# 130809_AriloTX_0_2.net
KiCad netlist of a schematic drawn in EAGLE
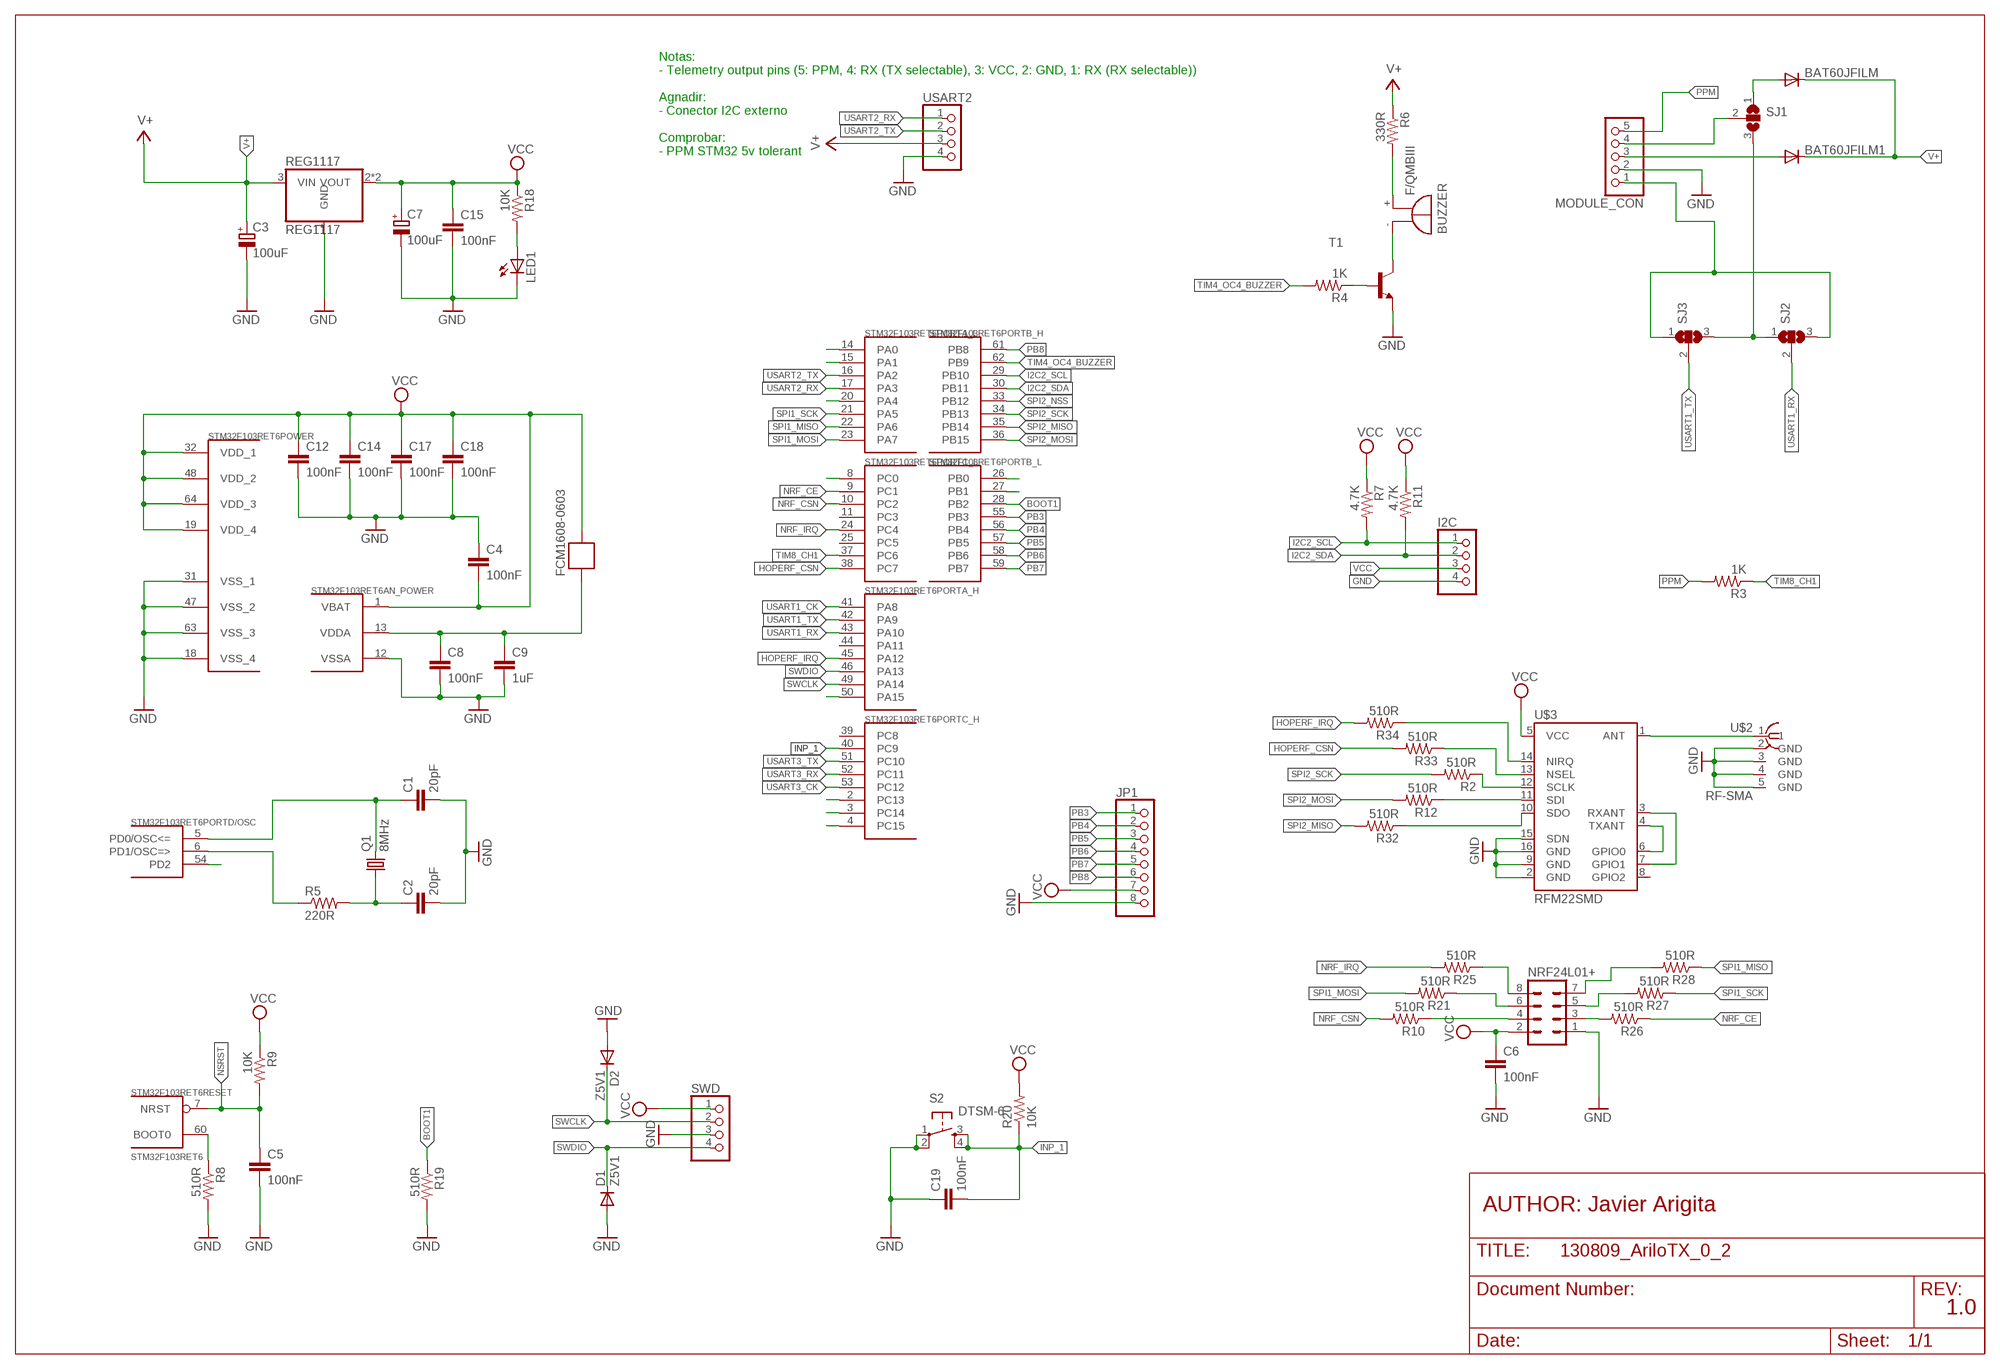
[diagram p0: schematic, sheet 1]

(export (version "E")
  (design (tool "Eeschema 10.0.6"))
  (components
    (comp (ref "BAT60JFILM")
      (value "DIODE-SOD323-R")
      (footprint "eagle-import:SOD323-R")
      (libsource (lib "eagle-import") (part "DIODE-SOD323-R"))
    )
    (comp (ref "BAT60JFILM1")
      (value "DIODE-SOD323-R")
      (footprint "eagle-import:SOD323-R")
      (libsource (lib "eagle-import") (part "DIODE-SOD323-R"))
    )
    (comp (ref "BUZZER")
      (value "F/QMBIII")
      (footprint "eagle-import:F_QMBIII")
      (libsource (lib "eagle-import") (part "F/QMBIII"))
    )
    (comp (ref "C1")
      (value "20pF")
      (footprint "eagle-import:C0805")
      (libsource (lib "eagle-import") (part "C-EUC0805"))
    )
    (comp (ref "C2")
      (value "20pF")
      (footprint "eagle-import:C0805")
      (libsource (lib "eagle-import") (part "C-EUC0805"))
    )
    (comp (ref "C3")
      (value "100uF")
      (footprint "eagle-import:SMC_B")
      (libsource (lib "eagle-import") (part "CPOL-EUSMCB"))
    )
    (comp (ref "C4")
      (value "100nF")
      (footprint "eagle-import:C0805")
      (libsource (lib "eagle-import") (part "C-EUC0805"))
    )
    (comp (ref "C5")
      (value "100nF")
      (footprint "eagle-import:C0805")
      (libsource (lib "eagle-import") (part "C-EUC0805"))
    )
    (comp (ref "C6")
      (value "100nF")
      (footprint "eagle-import:C0805")
      (libsource (lib "eagle-import") (part "C-EUC0805"))
    )
    (comp (ref "C7")
      (value "100uF")
      (footprint "eagle-import:SMC_B")
      (libsource (lib "eagle-import") (part "CPOL-EUSMCB"))
    )
    (comp (ref "C8")
      (value "100nF")
      (footprint "eagle-import:C0805")
      (libsource (lib "eagle-import") (part "C-EUC0805"))
    )
    (comp (ref "C9")
      (value "1uF")
      (footprint "eagle-import:C3216")
      (libsource (lib "eagle-import") (part "resistor_C-EUC3216"))
    )
    (comp (ref "C12")
      (value "100nF")
      (footprint "eagle-import:C0805")
      (libsource (lib "eagle-import") (part "C-EUC0805"))
    )
    (comp (ref "C14")
      (value "100nF")
      (footprint "eagle-import:C0805")
      (libsource (lib "eagle-import") (part "C-EUC0805"))
    )
    (comp (ref "C15")
      (value "100nF")
      (footprint "eagle-import:C0805")
      (libsource (lib "eagle-import") (part "C-EUC0805"))
    )
    (comp (ref "C17")
      (value "100nF")
      (footprint "eagle-import:C0805")
      (libsource (lib "eagle-import") (part "C-EUC0805"))
    )
    (comp (ref "C18")
      (value "100nF")
      (footprint "eagle-import:C0805")
      (libsource (lib "eagle-import") (part "C-EUC0805"))
    )
    (comp (ref "C19")
      (value "100nF")
      (footprint "eagle-import:C0805")
      (libsource (lib "eagle-import") (part "C-EUC0805"))
    )
    (comp (ref "D1")
      (value "Z5V1")
      (footprint "eagle-import:SOD323-R")
      (libsource (lib "eagle-import") (part "DIODE-SOD323-R"))
    )
    (comp (ref "D2")
      (value "Z5V1")
      (footprint "eagle-import:SOD323-R")
      (libsource (lib "eagle-import") (part "DIODE-SOD323-R"))
    )
    (comp (ref "FCM1608-0603")
      (value "FERRITE-BEAD")
      (footprint "eagle-import:R0603")
      (libsource (lib "eagle-import") (part "FERRITE-BEAD"))
    )
    (comp (ref "I2C")
      (value "PINHD-1X4")
      (footprint "eagle-import:1X04")
      (libsource (lib "eagle-import") (part "PINHD-1X4"))
    )
    (comp (ref "JP1")
      (value "PINHD-1X8")
      (footprint "eagle-import:1X08")
      (libsource (lib "eagle-import") (part "PINHD-1X8"))
    )
    (comp (ref "LED1")
      (value "LED0805")
      (footprint "eagle-import:CHIPLED_0805")
      (libsource (lib "eagle-import") (part "LED0805"))
    )
    (comp (ref "MODULE_CON")
      (value "PINHD-1X5")
      (footprint "eagle-import:1X05")
      (libsource (lib "eagle-import") (part "PINHD-1X5"))
    )
    (comp (ref "NRF24L01+")
      (value "MA04-2")
      (footprint "eagle-import:MA04-2")
      (libsource (lib "eagle-import") (part "MA04-2"))
    )
    (comp (ref "Q1")
      (value "8MHz")
      (footprint "eagle-import:SM49")
      (libsource (lib "eagle-import") (part "CRYSTALSM49"))
    )
    (comp (ref "R2")
      (value "510R")
      (footprint "eagle-import:R0805")
      (libsource (lib "eagle-import") (part "RESISTOR0805"))
    )
    (comp (ref "R3")
      (value "1K")
      (footprint "eagle-import:R0805")
      (libsource (lib "eagle-import") (part "RESISTOR0805"))
    )
    (comp (ref "R4")
      (value "1K")
      (footprint "eagle-import:R0805")
      (libsource (lib "eagle-import") (part "RESISTOR0805"))
    )
    (comp (ref "R5")
      (value "220R")
      (footprint "eagle-import:R0805")
      (libsource (lib "eagle-import") (part "RESISTOR0805"))
    )
    (comp (ref "R6")
      (value "330R")
      (footprint "eagle-import:R0805")
      (libsource (lib "eagle-import") (part "RESISTOR0805"))
    )
    (comp (ref "R7")
      (value "4.7K")
      (footprint "eagle-import:R0805")
      (libsource (lib "eagle-import") (part "RESISTOR0805"))
    )
    (comp (ref "R8")
      (value "510R")
      (footprint "eagle-import:R0805")
      (libsource (lib "eagle-import") (part "RESISTOR0805"))
    )
    (comp (ref "R9")
      (value "10K")
      (footprint "eagle-import:R0805")
      (libsource (lib "eagle-import") (part "RESISTOR0805"))
    )
    (comp (ref "R10")
      (value "510R")
      (footprint "eagle-import:R0805")
      (libsource (lib "eagle-import") (part "RESISTOR0805"))
    )
    (comp (ref "R11")
      (value "4.7K")
      (footprint "eagle-import:R0805")
      (libsource (lib "eagle-import") (part "RESISTOR0805"))
    )
    (comp (ref "R12")
      (value "510R")
      (footprint "eagle-import:R0805")
      (libsource (lib "eagle-import") (part "RESISTOR0805"))
    )
    (comp (ref "R18")
      (value "10K")
      (footprint "eagle-import:R0805")
      (libsource (lib "eagle-import") (part "RESISTOR0805"))
    )
    (comp (ref "R19")
      (value "510R")
      (footprint "eagle-import:R0805")
      (libsource (lib "eagle-import") (part "RESISTOR0805"))
    )
    (comp (ref "R20")
      (value "10K")
      (footprint "eagle-import:R0805")
      (libsource (lib "eagle-import") (part "RESISTOR0805"))
    )
    (comp (ref "R21")
      (value "510R")
      (footprint "eagle-import:R0805")
      (libsource (lib "eagle-import") (part "RESISTOR0805"))
    )
    (comp (ref "R25")
      (value "510R")
      (footprint "eagle-import:R0805")
      (libsource (lib "eagle-import") (part "RESISTOR0805"))
    )
    (comp (ref "R26")
      (value "510R")
      (footprint "eagle-import:R0805")
      (libsource (lib "eagle-import") (part "RESISTOR0805"))
    )
    (comp (ref "R27")
      (value "510R")
      (footprint "eagle-import:R0805")
      (libsource (lib "eagle-import") (part "RESISTOR0805"))
    )
    (comp (ref "R28")
      (value "510R")
      (footprint "eagle-import:R0805")
      (libsource (lib "eagle-import") (part "RESISTOR0805"))
    )
    (comp (ref "R32")
      (value "510R")
      (footprint "eagle-import:R0805")
      (libsource (lib "eagle-import") (part "RESISTOR0805"))
    )
    (comp (ref "R33")
      (value "510R")
      (footprint "eagle-import:R0805")
      (libsource (lib "eagle-import") (part "RESISTOR0805"))
    )
    (comp (ref "R34")
      (value "510R")
      (footprint "eagle-import:R0805")
      (libsource (lib "eagle-import") (part "RESISTOR0805"))
    )
    (comp (ref "REG1117")
      (value "REG1117")
      (footprint "eagle-import:SOT223")
      (libsource (lib "eagle-import") (part "REG1117"))
    )
    (comp (ref "S2")
      (value "DTSM-6")
      (footprint "eagle-import:DTSM-6")
      (libsource (lib "eagle-import") (part "DTSM-6"))
    )
    (comp (ref "SJ1")
      (value "SJ2W")
      (footprint "eagle-import:SJ_2")
      (libsource (lib "eagle-import") (part "SJ2W"))
    )
    (comp (ref "SJ2")
      (value "SJ2W")
      (footprint "eagle-import:SJ_2")
      (libsource (lib "eagle-import") (part "SJ2W"))
    )
    (comp (ref "SJ3")
      (value "SJ2W")
      (footprint "eagle-import:SJ_2")
      (libsource (lib "eagle-import") (part "SJ2W"))
    )
    (comp (ref "STM32F103RET6")
      (value "STM32F103RET6")
      (footprint "eagle-import:TQFP64")
      (libsource (lib "eagle-import") (part "STM32F10XRXT6"))
    )
    (comp (ref "SWD")
      (value "PINHD-1X4")
      (footprint "eagle-import:1X04")
      (libsource (lib "eagle-import") (part "PINHD-1X4"))
    )
    (comp (ref "T1")
      (value "BC848-NPN-SOT23-BEC")
      (footprint "eagle-import:SOT23-BEC")
      (libsource (lib "eagle-import") (part "-NPN-SOT23-BECBC848"))
    )
    (comp (ref "U$2")
      (value "RF-SMA")
      (footprint "eagle-import:BU-SMA-H")
      (libsource (lib "eagle-import") (part "RF-SMA"))
    )
    (comp (ref "U$3")
      (value "RFM22SMD")
      (footprint "eagle-import:RFM22-XXX-S2")
      (libsource (lib "eagle-import") (part "RFM22SMD"))
    )
    (comp (ref "USART2")
      (value "PINHD-1X4")
      (footprint "eagle-import:1X04")
      (libsource (lib "eagle-import") (part "PINHD-1X4"))
    )
  )
  (nets
    (net (code "1") (name "BOOT1") (class "Default")
      (node (ref "R19") (pin "1") (pinfunction "1_1") (pintype "passive"))
      (node (ref "STM32F103RET6") (pin "28") (pinfunction "PB2_28") (pintype "bidirectional"))
    )
    (net (code "2") (name "GND") (class "Default")
      (node (ref "C1") (pin "2") (pinfunction "2_2") (pintype "passive"))
      (node (ref "C12") (pin "2") (pinfunction "2_2") (pintype "passive"))
      (node (ref "C14") (pin "2") (pinfunction "2_2") (pintype "passive"))
      (node (ref "C15") (pin "2") (pinfunction "2_2") (pintype "passive"))
      (node (ref "C17") (pin "2") (pinfunction "2_2") (pintype "passive"))
      (node (ref "C18") (pin "2") (pinfunction "2_2") (pintype "passive"))
      (node (ref "C19") (pin "1") (pinfunction "1_1") (pintype "passive"))
      (node (ref "C2") (pin "2") (pinfunction "2_2") (pintype "passive"))
      (node (ref "C3") (pin "-") (pinfunction "-_-") (pintype "passive"))
      (node (ref "C4") (pin "1") (pinfunction "1_1") (pintype "passive"))
      (node (ref "C5") (pin "2") (pinfunction "2_2") (pintype "passive"))
      (node (ref "C6") (pin "2") (pinfunction "2_2") (pintype "passive"))
      (node (ref "C7") (pin "-") (pinfunction "-_-") (pintype "passive"))
      (node (ref "C8") (pin "2") (pinfunction "2_2") (pintype "passive"))
      (node (ref "C9") (pin "2") (pinfunction "2_2") (pintype "passive"))
      (node (ref "D1") (pin "A") (pinfunction "A_A") (pintype "passive"))
      (node (ref "D2") (pin "A") (pinfunction "A_A") (pintype "passive"))
      (node (ref "I2C") (pin "4") (pinfunction "4_4") (pintype "passive"))
      (node (ref "JP1") (pin "8") (pinfunction "8_8") (pintype "passive"))
      (node (ref "LED1") (pin "C") (pinfunction "C_C") (pintype "passive"))
      (node (ref "MODULE_CON") (pin "2") (pinfunction "2_2") (pintype "passive"))
      (node (ref "NRF24L01+") (pin "1") (pinfunction "1_1") (pintype "passive"))
      (node (ref "R19") (pin "2") (pinfunction "2_2") (pintype "passive"))
      (node (ref "R8") (pin "2") (pinfunction "2_2") (pintype "passive"))
      (node (ref "REG1117") (pin "1") (pinfunction "GND_1") (pintype "power_in"))
      (node (ref "S2") (pin "1") (pinfunction "1_1") (pintype "passive"))
      (node (ref "S2") (pin "2") (pinfunction "2_2") (pintype "passive"))
      (node (ref "STM32F103RET6") (pin "12") (pinfunction "VSSA_12") (pintype "power_in"))
      (node (ref "STM32F103RET6") (pin "18") (pinfunction "VSS_4_18") (pintype "power_in"))
      (node (ref "STM32F103RET6") (pin "31") (pinfunction "VSS_1_31") (pintype "power_in"))
      (node (ref "STM32F103RET6") (pin "47") (pinfunction "VSS_2_47") (pintype "power_in"))
      (node (ref "STM32F103RET6") (pin "63") (pinfunction "VSS_3_63") (pintype "power_in"))
      (node (ref "SWD") (pin "3") (pinfunction "3_3") (pintype "passive"))
      (node (ref "T1") (pin "E") (pinfunction "E_E") (pintype "passive"))
      (node (ref "U$2") (pin "2") (pinfunction "GND_2") (pintype "power_in"))
      (node (ref "U$2") (pin "3") (pinfunction "GND_3") (pintype "bidirectional"))
      (node (ref "U$2") (pin "4") (pinfunction "GND_4") (pintype "bidirectional"))
      (node (ref "U$2") (pin "5") (pinfunction "GND_5") (pintype "bidirectional"))
      (node (ref "U$3") (pin "15") (pinfunction "SDN_15") (pintype "input"))
      (node (ref "U$3") (pin "16") (pinfunction "GND_16") (pintype "power_in"))
      (node (ref "U$3") (pin "2") (pinfunction "GND_2") (pintype "power_in"))
      (node (ref "U$3") (pin "9") (pinfunction "GND_9") (pintype "power_in"))
      (node (ref "USART2") (pin "4") (pinfunction "4_4") (pintype "passive"))
    )
    (net (code "3") (name "HOPERF_CSN") (class "Default")
      (node (ref "R33") (pin "2") (pinfunction "2_2") (pintype "passive"))
      (node (ref "STM32F103RET6") (pin "38") (pinfunction "PC7_38") (pintype "bidirectional"))
    )
    (net (code "4") (name "HOPERF_IRQ") (class "Default")
      (node (ref "R34") (pin "2") (pinfunction "2_2") (pintype "passive"))
      (node (ref "STM32F103RET6") (pin "45") (pinfunction "PA12_45") (pintype "bidirectional"))
    )
    (net (code "5") (name "I2C2_SCL") (class "Default")
      (node (ref "I2C") (pin "1") (pinfunction "1_1") (pintype "passive"))
      (node (ref "R7") (pin "2") (pinfunction "2_2") (pintype "passive"))
      (node (ref "STM32F103RET6") (pin "29") (pinfunction "PB10_29") (pintype "bidirectional"))
    )
    (net (code "6") (name "I2C2_SDA") (class "Default")
      (node (ref "I2C") (pin "2") (pinfunction "2_2") (pintype "passive"))
      (node (ref "R11") (pin "2") (pinfunction "2_2") (pintype "passive"))
      (node (ref "STM32F103RET6") (pin "30") (pinfunction "PB11_30") (pintype "bidirectional"))
    )
    (net (code "7") (name "INP_1") (class "Default")
      (node (ref "C19") (pin "2") (pinfunction "2_2") (pintype "passive"))
      (node (ref "R20") (pin "1") (pinfunction "1_1") (pintype "passive"))
      (node (ref "S2") (pin "3") (pinfunction "3_3") (pintype "passive"))
      (node (ref "S2") (pin "4") (pinfunction "4_4") (pintype "passive"))
      (node (ref "STM32F103RET6") (pin "40") (pinfunction "PC9_40") (pintype "bidirectional"))
    )
    (net (code "8") (name "NRF_CE") (class "Default")
      (node (ref "R26") (pin "1") (pinfunction "1_1") (pintype "passive"))
      (node (ref "STM32F103RET6") (pin "9") (pinfunction "PC1_9") (pintype "bidirectional"))
    )
    (net (code "9") (name "NRF_CSN") (class "Default")
      (node (ref "R10") (pin "2") (pinfunction "2_2") (pintype "passive"))
      (node (ref "STM32F103RET6") (pin "10") (pinfunction "PC2_10") (pintype "bidirectional"))
    )
    (net (code "10") (name "NRF_IRQ") (class "Default")
      (node (ref "R25") (pin "2") (pinfunction "2_2") (pintype "passive"))
      (node (ref "STM32F103RET6") (pin "24") (pinfunction "PC4_24") (pintype "bidirectional"))
    )
    (net (code "11") (name "NSRST") (class "Default")
      (node (ref "C5") (pin "1") (pinfunction "1_1") (pintype "passive"))
      (node (ref "R9") (pin "2") (pinfunction "2_2") (pintype "passive"))
      (node (ref "STM32F103RET6") (pin "7") (pinfunction "NRST_7") (pintype "input"))
    )
    (net (code "12") (name "Net-(BAT60JFILM-PadA)") (class "Default")
      (node (ref "BAT60JFILM") (pin "A") (pinfunction "A_A") (pintype "passive"))
      (node (ref "SJ1") (pin "1") (pinfunction "1_1") (pintype "passive"))
    )
    (net (code "13") (name "Net-(BAT60JFILM1-PadA)") (class "Default")
      (node (ref "BAT60JFILM1") (pin "A") (pinfunction "A_A") (pintype "passive"))
      (node (ref "MODULE_CON") (pin "3") (pinfunction "3_3") (pintype "passive"))
    )
    (net (code "14") (name "Net-(BUZZER-+)") (class "Default")
      (node (ref "BUZZER") (pin "-") (pinfunction "+_-") (pintype "passive"))
      (node (ref "T1") (pin "C") (pinfunction "C_C") (pintype "passive"))
    )
    (net (code "15") (name "Net-(BUZZER--)") (class "Default")
      (node (ref "BUZZER") (pin "+") (pinfunction "-_+") (pintype "passive"))
      (node (ref "R6") (pin "2") (pinfunction "2_2") (pintype "passive"))
    )
    (net (code "16") (name "Net-(C2-Pad1)") (class "Default")
      (node (ref "C2") (pin "1") (pinfunction "1_1") (pintype "passive"))
      (node (ref "Q1") (pin "1") (pinfunction "1_1") (pintype "passive"))
      (node (ref "R5") (pin "2") (pinfunction "2_2") (pintype "passive"))
    )
    (net (code "17") (name "Net-(FCM1608-0603-P$2)") (class "Default")
      (node (ref "C8") (pin "1") (pinfunction "1_1") (pintype "passive"))
      (node (ref "C9") (pin "1") (pinfunction "1_1") (pintype "passive"))
      (node (ref "FCM1608-0603") (pin "2") (pinfunction "P$2_2") (pintype "bidirectional"))
      (node (ref "STM32F103RET6") (pin "13") (pinfunction "VDDA_13") (pintype "power_in"))
    )
    (net (code "18") (name "Net-(LED1-PadA)") (class "Default")
      (node (ref "LED1") (pin "A") (pinfunction "A_A") (pintype "passive"))
      (node (ref "R18") (pin "2") (pinfunction "2_2") (pintype "passive"))
    )
    (net (code "19") (name "Net-(MODULE_CON-Pad1)") (class "Default")
      (node (ref "MODULE_CON") (pin "1") (pinfunction "1_1") (pintype "passive"))
      (node (ref "SJ2") (pin "3") (pinfunction "3_3") (pintype "passive"))
      (node (ref "SJ3") (pin "1") (pinfunction "1_1") (pintype "passive"))
    )
    (net (code "20") (name "Net-(MODULE_CON-Pad4)") (class "Default")
      (node (ref "MODULE_CON") (pin "4") (pinfunction "4_4") (pintype "passive"))
      (node (ref "SJ1") (pin "2") (pinfunction "2_2") (pintype "passive"))
    )
    (net (code "21") (name "Net-(NRF24L01+-Pad3)") (class "Default")
      (node (ref "NRF24L01+") (pin "3") (pinfunction "3_3") (pintype "passive"))
      (node (ref "R26") (pin "2") (pinfunction "2_2") (pintype "passive"))
    )
    (net (code "22") (name "Net-(NRF24L01+-Pad4)") (class "Default")
      (node (ref "NRF24L01+") (pin "4") (pinfunction "4_4") (pintype "passive"))
      (node (ref "R10") (pin "1") (pinfunction "1_1") (pintype "passive"))
    )
    (net (code "23") (name "Net-(NRF24L01+-Pad5)") (class "Default")
      (node (ref "NRF24L01+") (pin "5") (pinfunction "5_5") (pintype "passive"))
      (node (ref "R27") (pin "2") (pinfunction "2_2") (pintype "passive"))
    )
    (net (code "24") (name "Net-(NRF24L01+-Pad6)") (class "Default")
      (node (ref "NRF24L01+") (pin "6") (pinfunction "6_6") (pintype "passive"))
      (node (ref "R21") (pin "1") (pinfunction "1_1") (pintype "passive"))
    )
    (net (code "25") (name "Net-(NRF24L01+-Pad7)") (class "Default")
      (node (ref "NRF24L01+") (pin "7") (pinfunction "7_7") (pintype "passive"))
      (node (ref "R28") (pin "2") (pinfunction "2_2") (pintype "passive"))
    )
    (net (code "26") (name "Net-(NRF24L01+-Pad8)") (class "Default")
      (node (ref "NRF24L01+") (pin "8") (pinfunction "8_8") (pintype "passive"))
      (node (ref "R25") (pin "1") (pinfunction "1_1") (pintype "passive"))
    )
    (net (code "27") (name "Net-(R4-Pad1)") (class "Default")
      (node (ref "R4") (pin "1") (pinfunction "1_1") (pintype "passive"))
      (node (ref "T1") (pin "B") (pinfunction "B_B") (pintype "passive"))
    )
    (net (code "28") (name "Net-(SJ1-Pad3)") (class "Default")
      (node (ref "SJ1") (pin "3") (pinfunction "3_3") (pintype "passive"))
      (node (ref "SJ2") (pin "1") (pinfunction "1_1") (pintype "passive"))
      (node (ref "SJ3") (pin "3") (pinfunction "3_3") (pintype "passive"))
    )
    (net (code "29") (name "Net-(STM32F103RET6H-PD0{slash}OSC<=)") (class "Default")
      (node (ref "C1") (pin "1") (pinfunction "1_1") (pintype "passive"))
      (node (ref "Q1") (pin "2") (pinfunction "2_2") (pintype "passive"))
      (node (ref "STM32F103RET6") (pin "5") (pinfunction "PD0/OSC<=_5") (pintype "bidirectional"))
    )
    (net (code "30") (name "Net-(STM32F103RET6H-PD1{slash}OSC=>)") (class "Default")
      (node (ref "R5") (pin "1") (pinfunction "1_1") (pintype "passive"))
      (node (ref "STM32F103RET6") (pin "6") (pinfunction "PD1/OSC=>_6") (pintype "bidirectional"))
    )
    (net (code "31") (name "Net-(STM32F103RET6J-BOOT0)") (class "Default")
      (node (ref "R8") (pin "1") (pinfunction "1_1") (pintype "passive"))
      (node (ref "STM32F103RET6") (pin "60") (pinfunction "BOOT0_60") (pintype "input"))
    )
    (net (code "32") (name "Net-(U$3-ANT)") (class "Default")
      (node (ref "U$2") (pin "1") (pinfunction "1_1") (pintype "passive"))
      (node (ref "U$3") (pin "1") (pinfunction "ANT_1") (pintype "bidirectional"))
    )
    (net (code "33") (name "Net-(U$3-GPIO0)") (class "Default")
      (node (ref "U$3") (pin "4") (pinfunction "TXANT_4") (pintype "input"))
      (node (ref "U$3") (pin "6") (pinfunction "GPIO0_6") (pintype "bidirectional"))
    )
    (net (code "34") (name "Net-(U$3-GPIO1)") (class "Default")
      (node (ref "U$3") (pin "3") (pinfunction "RXANT_3") (pintype "input"))
      (node (ref "U$3") (pin "7") (pinfunction "GPIO1_7") (pintype "bidirectional"))
    )
    (net (code "35") (name "Net-(U$3-NIRQ)") (class "Default")
      (node (ref "R34") (pin "1") (pinfunction "1_1") (pintype "passive"))
      (node (ref "U$3") (pin "14") (pinfunction "NIRQ_14") (pintype "output"))
    )
    (net (code "36") (name "Net-(U$3-NSEL)") (class "Default")
      (node (ref "R33") (pin "1") (pinfunction "1_1") (pintype "passive"))
      (node (ref "U$3") (pin "13") (pinfunction "NSEL_13") (pintype "input"))
    )
    (net (code "37") (name "Net-(U$3-SCLK)") (class "Default")
      (node (ref "R2") (pin "1") (pinfunction "1_1") (pintype "passive"))
      (node (ref "U$3") (pin "12") (pinfunction "SCLK_12") (pintype "input"))
    )
    (net (code "38") (name "Net-(U$3-SDI)") (class "Default")
      (node (ref "R12") (pin "1") (pinfunction "1_1") (pintype "passive"))
      (node (ref "U$3") (pin "11") (pinfunction "SDI_11") (pintype "input"))
    )
    (net (code "39") (name "Net-(U$3-SDO)") (class "Default")
      (node (ref "R32") (pin "1") (pinfunction "1_1") (pintype "passive"))
      (node (ref "U$3") (pin "10") (pinfunction "SDO_10") (pintype "output"))
    )
    (net (code "40") (name "PB3") (class "Default")
      (node (ref "JP1") (pin "1") (pinfunction "1_1") (pintype "passive"))
      (node (ref "STM32F103RET6") (pin "55") (pinfunction "PB3_55") (pintype "bidirectional"))
    )
    (net (code "41") (name "PB4") (class "Default")
      (node (ref "JP1") (pin "2") (pinfunction "2_2") (pintype "passive"))
      (node (ref "STM32F103RET6") (pin "56") (pinfunction "PB4_56") (pintype "bidirectional"))
    )
    (net (code "42") (name "PB5") (class "Default")
      (node (ref "JP1") (pin "3") (pinfunction "3_3") (pintype "passive"))
      (node (ref "STM32F103RET6") (pin "57") (pinfunction "PB5_57") (pintype "bidirectional"))
    )
    (net (code "43") (name "PB6") (class "Default")
      (node (ref "JP1") (pin "4") (pinfunction "4_4") (pintype "passive"))
      (node (ref "STM32F103RET6") (pin "58") (pinfunction "PB6_58") (pintype "bidirectional"))
    )
    (net (code "44") (name "PB7") (class "Default")
      (node (ref "JP1") (pin "5") (pinfunction "5_5") (pintype "passive"))
      (node (ref "STM32F103RET6") (pin "59") (pinfunction "PB7_59") (pintype "bidirectional"))
    )
    (net (code "45") (name "PB8") (class "Default")
      (node (ref "JP1") (pin "6") (pinfunction "6_6") (pintype "passive"))
      (node (ref "STM32F103RET6") (pin "61") (pinfunction "PB8_61") (pintype "bidirectional"))
    )
    (net (code "46") (name "PPM") (class "Default")
      (node (ref "MODULE_CON") (pin "5") (pinfunction "5_5") (pintype "passive"))
      (node (ref "R3") (pin "2") (pinfunction "2_2") (pintype "passive"))
    )
    (net (code "47") (name "SPI1_MISO") (class "Default")
      (node (ref "R28") (pin "1") (pinfunction "1_1") (pintype "passive"))
      (node (ref "STM32F103RET6") (pin "22") (pinfunction "PA6_22") (pintype "bidirectional"))
    )
    (net (code "48") (name "SPI1_MOSI") (class "Default")
      (node (ref "R21") (pin "2") (pinfunction "2_2") (pintype "passive"))
      (node (ref "STM32F103RET6") (pin "23") (pinfunction "PA7_23") (pintype "bidirectional"))
    )
    (net (code "49") (name "SPI1_SCK") (class "Default")
      (node (ref "R27") (pin "1") (pinfunction "1_1") (pintype "passive"))
      (node (ref "STM32F103RET6") (pin "21") (pinfunction "PA5_21") (pintype "bidirectional"))
    )
    (net (code "50") (name "SPI2_MISO") (class "Default")
      (node (ref "R32") (pin "2") (pinfunction "2_2") (pintype "passive"))
      (node (ref "STM32F103RET6") (pin "35") (pinfunction "PB14_35") (pintype "bidirectional"))
    )
    (net (code "51") (name "SPI2_MOSI") (class "Default")
      (node (ref "R12") (pin "2") (pinfunction "2_2") (pintype "passive"))
      (node (ref "STM32F103RET6") (pin "36") (pinfunction "PB15_36") (pintype "bidirectional"))
    )
    (net (code "52") (name "SPI2_NSS") (class "Default")
      (node (ref "STM32F103RET6") (pin "33") (pinfunction "PB12_33") (pintype "bidirectional"))
    )
    (net (code "53") (name "SPI2_SCK") (class "Default")
      (node (ref "R2") (pin "2") (pinfunction "2_2") (pintype "passive"))
      (node (ref "STM32F103RET6") (pin "34") (pinfunction "PB13_34") (pintype "bidirectional"))
    )
    (net (code "54") (name "SWCLK") (class "Default")
      (node (ref "D2") (pin "C") (pinfunction "C_C") (pintype "passive"))
      (node (ref "STM32F103RET6") (pin "49") (pinfunction "PA14_49") (pintype "bidirectional"))
      (node (ref "SWD") (pin "2") (pinfunction "2_2") (pintype "passive"))
    )
    (net (code "55") (name "SWDIO") (class "Default")
      (node (ref "D1") (pin "C") (pinfunction "C_C") (pintype "passive"))
      (node (ref "STM32F103RET6") (pin "46") (pinfunction "PA13_46") (pintype "bidirectional"))
      (node (ref "SWD") (pin "4") (pinfunction "4_4") (pintype "passive"))
    )
    (net (code "56") (name "TIM4_OC4_BUZZER") (class "Default")
      (node (ref "R4") (pin "2") (pinfunction "2_2") (pintype "passive"))
      (node (ref "STM32F103RET6") (pin "62") (pinfunction "PB9_62") (pintype "bidirectional"))
    )
    (net (code "57") (name "TIM8_CH1") (class "Default")
      (node (ref "R3") (pin "1") (pinfunction "1_1") (pintype "passive"))
      (node (ref "STM32F103RET6") (pin "37") (pinfunction "PC6_37") (pintype "bidirectional"))
    )
    (net (code "58") (name "USART1_CK") (class "Default")
      (node (ref "STM32F103RET6") (pin "41") (pinfunction "PA8_41") (pintype "bidirectional"))
    )
    (net (code "59") (name "USART1_RX") (class "Default")
      (node (ref "SJ2") (pin "2") (pinfunction "2_2") (pintype "passive"))
      (node (ref "STM32F103RET6") (pin "43") (pinfunction "PA10_43") (pintype "bidirectional"))
    )
    (net (code "60") (name "USART1_TX") (class "Default")
      (node (ref "SJ3") (pin "2") (pinfunction "2_2") (pintype "passive"))
      (node (ref "STM32F103RET6") (pin "42") (pinfunction "PA9_42") (pintype "bidirectional"))
    )
    (net (code "61") (name "USART2_RX") (class "Default")
      (node (ref "STM32F103RET6") (pin "17") (pinfunction "PA3_17") (pintype "bidirectional"))
      (node (ref "USART2") (pin "1") (pinfunction "1_1") (pintype "passive"))
    )
    (net (code "62") (name "USART2_TX") (class "Default")
      (node (ref "STM32F103RET6") (pin "16") (pinfunction "PA2_16") (pintype "bidirectional"))
      (node (ref "USART2") (pin "2") (pinfunction "2_2") (pintype "passive"))
    )
    (net (code "63") (name "USART3_CK") (class "Default")
      (node (ref "STM32F103RET6") (pin "53") (pinfunction "PC12_53") (pintype "bidirectional"))
    )
    (net (code "64") (name "USART3_RX") (class "Default")
      (node (ref "STM32F103RET6") (pin "52") (pinfunction "PC11_52") (pintype "bidirectional"))
    )
    (net (code "65") (name "USART3_TX") (class "Default")
      (node (ref "STM32F103RET6") (pin "51") (pinfunction "PC10_51") (pintype "bidirectional"))
    )
    (net (code "66") (name "V+") (class "Default")
      (node (ref "BAT60JFILM") (pin "C") (pinfunction "C_C") (pintype "passive"))
      (node (ref "BAT60JFILM1") (pin "C") (pinfunction "C_C") (pintype "passive"))
      (node (ref "C3") (pin "+") (pinfunction "+_+") (pintype "passive"))
      (node (ref "R6") (pin "1") (pinfunction "1_1") (pintype "passive"))
      (node (ref "REG1117") (pin "3") (pinfunction "VIN_3") (pintype "input"))
      (node (ref "USART2") (pin "3") (pinfunction "3_3") (pintype "passive"))
    )
    (net (code "67") (name "VCC") (class "Default")
      (node (ref "C12") (pin "1") (pinfunction "1_1") (pintype "passive"))
      (node (ref "C14") (pin "1") (pinfunction "1_1") (pintype "passive"))
      (node (ref "C15") (pin "1") (pinfunction "1_1") (pintype "passive"))
      (node (ref "C17") (pin "1") (pinfunction "1_1") (pintype "passive"))
      (node (ref "C18") (pin "1") (pinfunction "1_1") (pintype "passive"))
      (node (ref "C4") (pin "2") (pinfunction "2_2") (pintype "passive"))
      (node (ref "C6") (pin "1") (pinfunction "1_1") (pintype "passive"))
      (node (ref "C7") (pin "+") (pinfunction "+_+") (pintype "passive"))
      (node (ref "FCM1608-0603") (pin "1") (pinfunction "P$1_1") (pintype "bidirectional"))
      (node (ref "I2C") (pin "3") (pinfunction "3_3") (pintype "passive"))
      (node (ref "JP1") (pin "7") (pinfunction "7_7") (pintype "passive"))
      (node (ref "NRF24L01+") (pin "2") (pinfunction "2_2") (pintype "passive"))
      (node (ref "R11") (pin "1") (pinfunction "1_1") (pintype "passive"))
      (node (ref "R18") (pin "1") (pinfunction "1_1") (pintype "passive"))
      (node (ref "R20") (pin "2") (pinfunction "2_2") (pintype "passive"))
      (node (ref "R7") (pin "1") (pinfunction "1_1") (pintype "passive"))
      (node (ref "R9") (pin "1") (pinfunction "1_1") (pintype "passive"))
      (node (ref "REG1117") (pin "2") (pinfunction "VOUT_2") (pintype "power_in"))
      (node (ref "REG1117") (pin "4") (pinfunction "VOUT_4") (pintype "power_in"))
      (node (ref "STM32F103RET6") (pin "1") (pinfunction "VBAT_1") (pintype "power_in"))
      (node (ref "STM32F103RET6") (pin "19") (pinfunction "VDD_4_19") (pintype "power_in"))
      (node (ref "STM32F103RET6") (pin "32") (pinfunction "VDD_1_32") (pintype "power_in"))
      (node (ref "STM32F103RET6") (pin "48") (pinfunction "VDD_2_48") (pintype "power_in"))
      (node (ref "STM32F103RET6") (pin "64") (pinfunction "VDD_3_64") (pintype "power_in"))
      (node (ref "SWD") (pin "1") (pinfunction "1_1") (pintype "passive"))
      (node (ref "U$3") (pin "5") (pinfunction "VCC_5") (pintype "bidirectional"))
    )
    (net (code "68") (name "unconnected-(STM32F103RET6B-PA11-Pad44)") (class "Default")
      (node (ref "STM32F103RET6") (pin "44") (pinfunction "PA11_44") (pintype "bidirectional"))
    )
    (net (code "69") (name "unconnected-(STM32F103RET6B-PA15-Pad50)") (class "Default")
      (node (ref "STM32F103RET6") (pin "50") (pinfunction "PA15_50") (pintype "bidirectional"))
    )
    (net (code "70") (name "unconnected-(STM32F103RET6C-PA0-Pad14)") (class "Default")
      (node (ref "STM32F103RET6") (pin "14") (pinfunction "PA0_14") (pintype "bidirectional"))
    )
    (net (code "71") (name "unconnected-(STM32F103RET6C-PA1-Pad15)") (class "Default")
      (node (ref "STM32F103RET6") (pin "15") (pinfunction "PA1_15") (pintype "bidirectional"))
    )
    (net (code "72") (name "unconnected-(STM32F103RET6C-PA4-Pad20)") (class "Default")
      (node (ref "STM32F103RET6") (pin "20") (pinfunction "PA4_20") (pintype "bidirectional"))
    )
    (net (code "73") (name "unconnected-(STM32F103RET6E-PB0-Pad26)") (class "Default")
      (node (ref "STM32F103RET6") (pin "26") (pinfunction "PB0_26") (pintype "bidirectional"))
    )
    (net (code "74") (name "unconnected-(STM32F103RET6E-PB1-Pad27)") (class "Default")
      (node (ref "STM32F103RET6") (pin "27") (pinfunction "PB1_27") (pintype "bidirectional"))
    )
    (net (code "75") (name "unconnected-(STM32F103RET6F-PC8-Pad39)") (class "Default")
      (node (ref "STM32F103RET6") (pin "39") (pinfunction "PC8_39") (pintype "bidirectional"))
    )
    (net (code "76") (name "unconnected-(STM32F103RET6F-PC13-Pad2)") (class "Default")
      (node (ref "STM32F103RET6") (pin "2") (pinfunction "PC13_2") (pintype "bidirectional"))
    )
    (net (code "77") (name "unconnected-(STM32F103RET6F-PC14-Pad3)") (class "Default")
      (node (ref "STM32F103RET6") (pin "3") (pinfunction "PC14_3") (pintype "bidirectional"))
    )
    (net (code "78") (name "unconnected-(STM32F103RET6F-PC15-Pad4)") (class "Default")
      (node (ref "STM32F103RET6") (pin "4") (pinfunction "PC15_4") (pintype "bidirectional"))
    )
    (net (code "79") (name "unconnected-(STM32F103RET6G-PC0-Pad8)") (class "Default")
      (node (ref "STM32F103RET6") (pin "8") (pinfunction "PC0_8") (pintype "bidirectional"))
    )
    (net (code "80") (name "unconnected-(STM32F103RET6G-PC3-Pad11)") (class "Default")
      (node (ref "STM32F103RET6") (pin "11") (pinfunction "PC3_11") (pintype "bidirectional"))
    )
    (net (code "81") (name "unconnected-(STM32F103RET6G-PC5-Pad25)") (class "Default")
      (node (ref "STM32F103RET6") (pin "25") (pinfunction "PC5_25") (pintype "bidirectional"))
    )
    (net (code "82") (name "unconnected-(STM32F103RET6H-PD2-Pad54)") (class "Default")
      (node (ref "STM32F103RET6") (pin "54") (pinfunction "PD2_54") (pintype "bidirectional"))
    )
    (net (code "83") (name "unconnected-(U$3-GPIO2-Pad8)") (class "Default")
      (node (ref "U$3") (pin "8") (pinfunction "GPIO2_8") (pintype "bidirectional"))
    )
  )
)
